# DetBackplane01.net
KiCad netlist of a schematic drawn in EAGLE
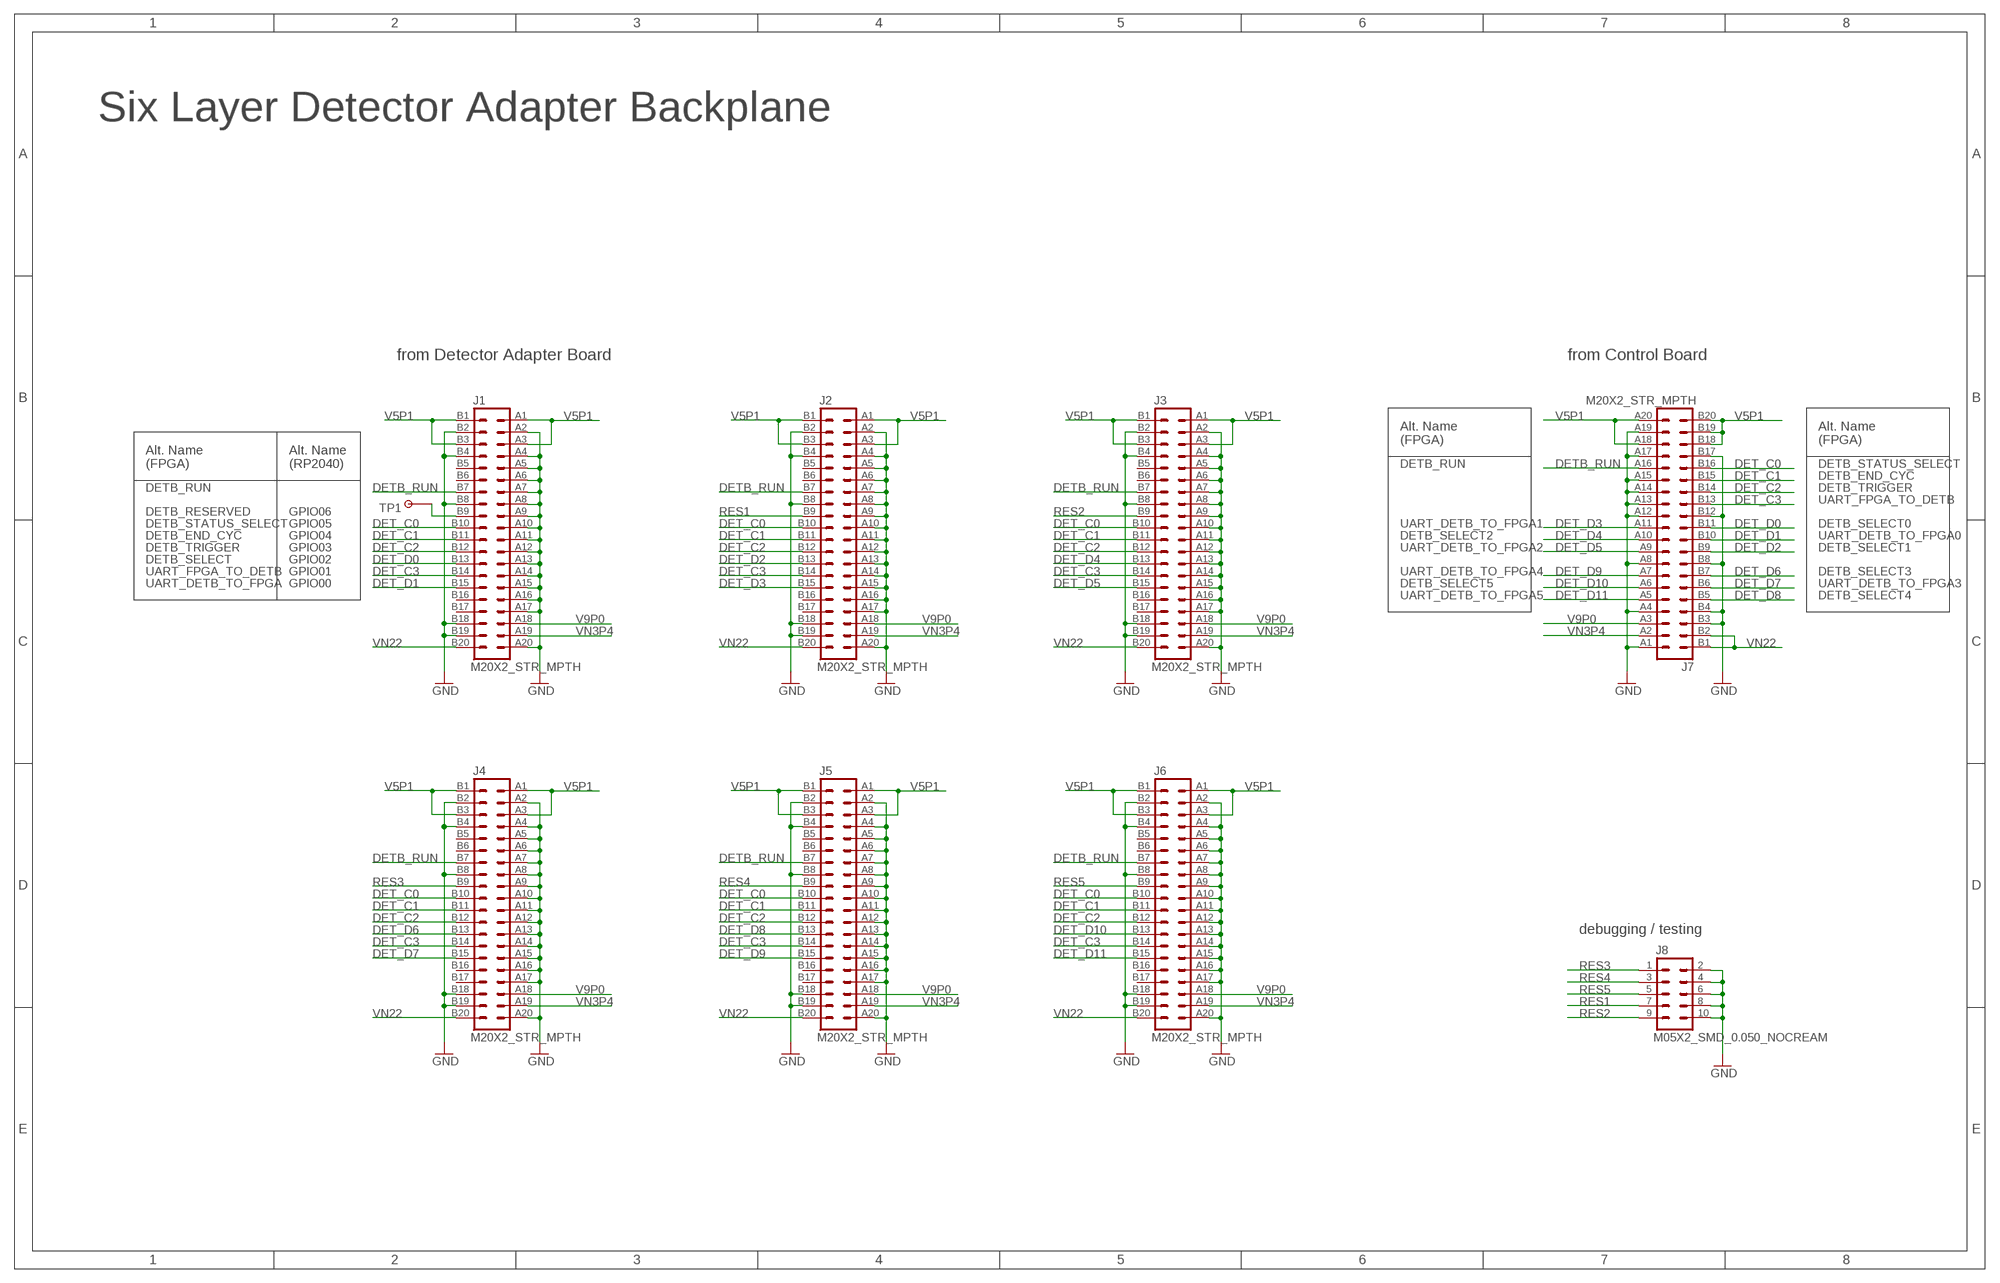
[diagram p0: schematic, sheet 1]

(export (version "E")
  (design (tool "Eeschema 10.0.6"))
  (components
    (comp (ref "J1")
      (value "M20X2_STR_MPTH")
      (footprint "eagle-import:M20X2_HARFLEX_F_STR_MPTH")
      (libsource (lib "eagle-import") (part "M20X2_STR_MPTH"))
    )
    (comp (ref "J2")
      (value "M20X2_STR_MPTH")
      (footprint "eagle-import:M20X2_HARFLEX_F_STR_MPTH")
      (libsource (lib "eagle-import") (part "M20X2_STR_MPTH"))
    )
    (comp (ref "J3")
      (value "M20X2_STR_MPTH")
      (footprint "eagle-import:M20X2_HARFLEX_F_STR_MPTH")
      (libsource (lib "eagle-import") (part "M20X2_STR_MPTH"))
    )
    (comp (ref "J4")
      (value "M20X2_STR_MPTH")
      (footprint "eagle-import:M20X2_HARFLEX_F_STR_MPTH")
      (libsource (lib "eagle-import") (part "M20X2_STR_MPTH"))
    )
    (comp (ref "J5")
      (value "M20X2_STR_MPTH")
      (footprint "eagle-import:M20X2_HARFLEX_F_STR_MPTH")
      (libsource (lib "eagle-import") (part "M20X2_STR_MPTH"))
    )
    (comp (ref "J6")
      (value "M20X2_STR_MPTH")
      (footprint "eagle-import:M20X2_HARFLEX_F_STR_MPTH")
      (libsource (lib "eagle-import") (part "M20X2_STR_MPTH"))
    )
    (comp (ref "J7")
      (value "M20X2_STR_MPTH")
      (footprint "eagle-import:M20X2_HARFLEX_F_STR_MPTH")
      (libsource (lib "eagle-import") (part "M20X2_STR_MPTH"))
    )
    (comp (ref "J8")
      (value "M05X2_SMD_0.050_NOCREAM")
      (footprint "eagle-import:M05X2_0.050_SMD_NO_CREAM")
      (libsource (lib "eagle-import") (part "M05X2_SMD_0.050_NOCREAM"))
    )
    (comp (ref "TP1")
      (value "TESTPOINT_ROUND")
      (footprint "eagle-import:TESTPAD_ROUND")
      (libsource (lib "eagle-import") (part "TESTPOINT_ROUND"))
    )
  )
  (nets
    (net (code "1") (name "/DETB_RUN") (class "Default")
      (node (ref "J1") (pin "B7") (pinfunction "13_B7") (pintype "passive"))
      (node (ref "J2") (pin "B7") (pinfunction "13_B7") (pintype "passive"))
      (node (ref "J3") (pin "B7") (pinfunction "13_B7") (pintype "passive"))
      (node (ref "J4") (pin "B7") (pinfunction "13_B7") (pintype "passive"))
      (node (ref "J5") (pin "B7") (pinfunction "13_B7") (pintype "passive"))
      (node (ref "J6") (pin "B7") (pinfunction "13_B7") (pintype "passive"))
      (node (ref "J7") (pin "A16") (pinfunction "32_A16") (pintype "passive"))
    )
    (net (code "2") (name "/DET_C0") (class "Default")
      (node (ref "J1") (pin "B10") (pinfunction "19_B10") (pintype "passive"))
      (node (ref "J2") (pin "B10") (pinfunction "19_B10") (pintype "passive"))
      (node (ref "J3") (pin "B10") (pinfunction "19_B10") (pintype "passive"))
      (node (ref "J4") (pin "B10") (pinfunction "19_B10") (pintype "passive"))
      (node (ref "J5") (pin "B10") (pinfunction "19_B10") (pintype "passive"))
      (node (ref "J6") (pin "B10") (pinfunction "19_B10") (pintype "passive"))
      (node (ref "J7") (pin "B16") (pinfunction "31_B16") (pintype "passive"))
    )
    (net (code "3") (name "/DET_C1") (class "Default")
      (node (ref "J1") (pin "B11") (pinfunction "21_B11") (pintype "passive"))
      (node (ref "J2") (pin "B11") (pinfunction "21_B11") (pintype "passive"))
      (node (ref "J3") (pin "B11") (pinfunction "21_B11") (pintype "passive"))
      (node (ref "J4") (pin "B11") (pinfunction "21_B11") (pintype "passive"))
      (node (ref "J5") (pin "B11") (pinfunction "21_B11") (pintype "passive"))
      (node (ref "J6") (pin "B11") (pinfunction "21_B11") (pintype "passive"))
      (node (ref "J7") (pin "B15") (pinfunction "29_B15") (pintype "passive"))
    )
    (net (code "4") (name "/DET_C2") (class "Default")
      (node (ref "J1") (pin "B12") (pinfunction "23_B12") (pintype "passive"))
      (node (ref "J2") (pin "B12") (pinfunction "23_B12") (pintype "passive"))
      (node (ref "J3") (pin "B12") (pinfunction "23_B12") (pintype "passive"))
      (node (ref "J4") (pin "B12") (pinfunction "23_B12") (pintype "passive"))
      (node (ref "J5") (pin "B12") (pinfunction "23_B12") (pintype "passive"))
      (node (ref "J6") (pin "B12") (pinfunction "23_B12") (pintype "passive"))
      (node (ref "J7") (pin "B14") (pinfunction "27_B14") (pintype "passive"))
    )
    (net (code "5") (name "/DET_C3") (class "Default")
      (node (ref "J1") (pin "B14") (pinfunction "27_B14") (pintype "passive"))
      (node (ref "J2") (pin "B14") (pinfunction "27_B14") (pintype "passive"))
      (node (ref "J3") (pin "B14") (pinfunction "27_B14") (pintype "passive"))
      (node (ref "J4") (pin "B14") (pinfunction "27_B14") (pintype "passive"))
      (node (ref "J5") (pin "B14") (pinfunction "27_B14") (pintype "passive"))
      (node (ref "J6") (pin "B14") (pinfunction "27_B14") (pintype "passive"))
      (node (ref "J7") (pin "B13") (pinfunction "25_B13") (pintype "passive"))
    )
    (net (code "6") (name "/DET_D0") (class "Default")
      (node (ref "J1") (pin "B13") (pinfunction "25_B13") (pintype "passive"))
      (node (ref "J7") (pin "B11") (pinfunction "21_B11") (pintype "passive"))
    )
    (net (code "7") (name "/DET_D1") (class "Default")
      (node (ref "J1") (pin "B15") (pinfunction "29_B15") (pintype "passive"))
      (node (ref "J7") (pin "B10") (pinfunction "19_B10") (pintype "passive"))
    )
    (net (code "8") (name "/DET_D2") (class "Default")
      (node (ref "J2") (pin "B13") (pinfunction "25_B13") (pintype "passive"))
      (node (ref "J7") (pin "B9") (pinfunction "17_B9") (pintype "passive"))
    )
    (net (code "9") (name "/DET_D3") (class "Default")
      (node (ref "J2") (pin "B15") (pinfunction "29_B15") (pintype "passive"))
      (node (ref "J7") (pin "A11") (pinfunction "22_A11") (pintype "passive"))
    )
    (net (code "10") (name "/DET_D4") (class "Default")
      (node (ref "J3") (pin "B13") (pinfunction "25_B13") (pintype "passive"))
      (node (ref "J7") (pin "A10") (pinfunction "20_A10") (pintype "passive"))
    )
    (net (code "11") (name "/DET_D5") (class "Default")
      (node (ref "J3") (pin "B15") (pinfunction "29_B15") (pintype "passive"))
      (node (ref "J7") (pin "A9") (pinfunction "18_A9") (pintype "passive"))
    )
    (net (code "12") (name "/DET_D6") (class "Default")
      (node (ref "J4") (pin "B13") (pinfunction "25_B13") (pintype "passive"))
      (node (ref "J7") (pin "B7") (pinfunction "13_B7") (pintype "passive"))
    )
    (net (code "13") (name "/DET_D7") (class "Default")
      (node (ref "J4") (pin "B15") (pinfunction "29_B15") (pintype "passive"))
      (node (ref "J7") (pin "B6") (pinfunction "11_B6") (pintype "passive"))
    )
    (net (code "14") (name "/DET_D8") (class "Default")
      (node (ref "J5") (pin "B13") (pinfunction "25_B13") (pintype "passive"))
      (node (ref "J7") (pin "B5") (pinfunction "9_B5") (pintype "passive"))
    )
    (net (code "15") (name "/DET_D9") (class "Default")
      (node (ref "J5") (pin "B15") (pinfunction "29_B15") (pintype "passive"))
      (node (ref "J7") (pin "A7") (pinfunction "14_A7") (pintype "passive"))
    )
    (net (code "16") (name "/DET_D10") (class "Default")
      (node (ref "J6") (pin "B13") (pinfunction "25_B13") (pintype "passive"))
      (node (ref "J7") (pin "A6") (pinfunction "12_A6") (pintype "passive"))
    )
    (net (code "17") (name "/DET_D11") (class "Default")
      (node (ref "J6") (pin "B15") (pinfunction "29_B15") (pintype "passive"))
      (node (ref "J7") (pin "A5") (pinfunction "10_A5") (pintype "passive"))
    )
    (net (code "18") (name "/RES1") (class "Default")
      (node (ref "J2") (pin "B9") (pinfunction "17_B9") (pintype "passive"))
      (node (ref "J8") (pin "7") (pinfunction "7_7") (pintype "passive"))
    )
    (net (code "19") (name "/RES2") (class "Default")
      (node (ref "J3") (pin "B9") (pinfunction "17_B9") (pintype "passive"))
      (node (ref "J8") (pin "9") (pinfunction "9_9") (pintype "passive"))
    )
    (net (code "20") (name "/RES3") (class "Default")
      (node (ref "J4") (pin "B9") (pinfunction "17_B9") (pintype "passive"))
      (node (ref "J8") (pin "1") (pinfunction "1_1") (pintype "passive"))
    )
    (net (code "21") (name "/RES4") (class "Default")
      (node (ref "J5") (pin "B9") (pinfunction "17_B9") (pintype "passive"))
      (node (ref "J8") (pin "3") (pinfunction "3_3") (pintype "passive"))
    )
    (net (code "22") (name "/RES5") (class "Default")
      (node (ref "J6") (pin "B9") (pinfunction "17_B9") (pintype "passive"))
      (node (ref "J8") (pin "5") (pinfunction "5_5") (pintype "passive"))
    )
    (net (code "23") (name "/V5P1") (class "Default")
      (node (ref "J1") (pin "A1") (pinfunction "2_A1") (pintype "passive"))
      (node (ref "J1") (pin "A3") (pinfunction "6_A3") (pintype "passive"))
      (node (ref "J1") (pin "B1") (pinfunction "1_B1") (pintype "passive"))
      (node (ref "J1") (pin "B3") (pinfunction "5_B3") (pintype "passive"))
      (node (ref "J2") (pin "A1") (pinfunction "2_A1") (pintype "passive"))
      (node (ref "J2") (pin "A3") (pinfunction "6_A3") (pintype "passive"))
      (node (ref "J2") (pin "B1") (pinfunction "1_B1") (pintype "passive"))
      (node (ref "J2") (pin "B3") (pinfunction "5_B3") (pintype "passive"))
      (node (ref "J3") (pin "A1") (pinfunction "2_A1") (pintype "passive"))
      (node (ref "J3") (pin "A3") (pinfunction "6_A3") (pintype "passive"))
      (node (ref "J3") (pin "B1") (pinfunction "1_B1") (pintype "passive"))
      (node (ref "J3") (pin "B3") (pinfunction "5_B3") (pintype "passive"))
      (node (ref "J4") (pin "A1") (pinfunction "2_A1") (pintype "passive"))
      (node (ref "J4") (pin "A3") (pinfunction "6_A3") (pintype "passive"))
      (node (ref "J4") (pin "B1") (pinfunction "1_B1") (pintype "passive"))
      (node (ref "J4") (pin "B3") (pinfunction "5_B3") (pintype "passive"))
      (node (ref "J5") (pin "A1") (pinfunction "2_A1") (pintype "passive"))
      (node (ref "J5") (pin "A3") (pinfunction "6_A3") (pintype "passive"))
      (node (ref "J5") (pin "B1") (pinfunction "1_B1") (pintype "passive"))
      (node (ref "J5") (pin "B3") (pinfunction "5_B3") (pintype "passive"))
      (node (ref "J6") (pin "A1") (pinfunction "2_A1") (pintype "passive"))
      (node (ref "J6") (pin "A3") (pinfunction "6_A3") (pintype "passive"))
      (node (ref "J6") (pin "B1") (pinfunction "1_B1") (pintype "passive"))
      (node (ref "J6") (pin "B3") (pinfunction "5_B3") (pintype "passive"))
      (node (ref "J7") (pin "A18") (pinfunction "36_A18") (pintype "passive"))
      (node (ref "J7") (pin "A20") (pinfunction "40_A20") (pintype "passive"))
      (node (ref "J7") (pin "B18") (pinfunction "35_B18") (pintype "passive"))
      (node (ref "J7") (pin "B19") (pinfunction "37_B19") (pintype "passive"))
      (node (ref "J7") (pin "B20") (pinfunction "39_B20") (pintype "passive"))
    )
    (net (code "24") (name "/V9P0") (class "Default")
      (node (ref "J1") (pin "A18") (pinfunction "36_A18") (pintype "passive"))
      (node (ref "J2") (pin "A18") (pinfunction "36_A18") (pintype "passive"))
      (node (ref "J3") (pin "A18") (pinfunction "36_A18") (pintype "passive"))
      (node (ref "J4") (pin "A18") (pinfunction "36_A18") (pintype "passive"))
      (node (ref "J5") (pin "A18") (pinfunction "36_A18") (pintype "passive"))
      (node (ref "J6") (pin "A18") (pinfunction "36_A18") (pintype "passive"))
      (node (ref "J7") (pin "A3") (pinfunction "6_A3") (pintype "passive"))
    )
    (net (code "25") (name "/VN3P4") (class "Default")
      (node (ref "J1") (pin "A19") (pinfunction "38_A19") (pintype "passive"))
      (node (ref "J2") (pin "A19") (pinfunction "38_A19") (pintype "passive"))
      (node (ref "J3") (pin "A19") (pinfunction "38_A19") (pintype "passive"))
      (node (ref "J4") (pin "A19") (pinfunction "38_A19") (pintype "passive"))
      (node (ref "J5") (pin "A19") (pinfunction "38_A19") (pintype "passive"))
      (node (ref "J6") (pin "A19") (pinfunction "38_A19") (pintype "passive"))
      (node (ref "J7") (pin "A2") (pinfunction "4_A2") (pintype "passive"))
    )
    (net (code "26") (name "/VN22") (class "Default")
      (node (ref "J1") (pin "B20") (pinfunction "39_B20") (pintype "passive"))
      (node (ref "J2") (pin "B20") (pinfunction "39_B20") (pintype "passive"))
      (node (ref "J3") (pin "B20") (pinfunction "39_B20") (pintype "passive"))
      (node (ref "J4") (pin "B20") (pinfunction "39_B20") (pintype "passive"))
      (node (ref "J5") (pin "B20") (pinfunction "39_B20") (pintype "passive"))
      (node (ref "J6") (pin "B20") (pinfunction "39_B20") (pintype "passive"))
      (node (ref "J7") (pin "B1") (pinfunction "1_B1") (pintype "passive"))
      (node (ref "J7") (pin "B2") (pinfunction "3_B2") (pintype "passive"))
    )
    (net (code "27") (name "GND") (class "Default")
      (node (ref "J1") (pin "A10") (pinfunction "20_A10") (pintype "passive"))
      (node (ref "J1") (pin "A11") (pinfunction "22_A11") (pintype "passive"))
      (node (ref "J1") (pin "A12") (pinfunction "24_A12") (pintype "passive"))
      (node (ref "J1") (pin "A13") (pinfunction "26_A13") (pintype "passive"))
      (node (ref "J1") (pin "A14") (pinfunction "28_A14") (pintype "passive"))
      (node (ref "J1") (pin "A15") (pinfunction "30_A15") (pintype "passive"))
      (node (ref "J1") (pin "A16") (pinfunction "32_A16") (pintype "passive"))
      (node (ref "J1") (pin "A17") (pinfunction "34_A17") (pintype "passive"))
      (node (ref "J1") (pin "A2") (pinfunction "4_A2") (pintype "passive"))
      (node (ref "J1") (pin "A20") (pinfunction "40_A20") (pintype "passive"))
      (node (ref "J1") (pin "A4") (pinfunction "8_A4") (pintype "passive"))
      (node (ref "J1") (pin "A5") (pinfunction "10_A5") (pintype "passive"))
      (node (ref "J1") (pin "A6") (pinfunction "12_A6") (pintype "passive"))
      (node (ref "J1") (pin "A7") (pinfunction "14_A7") (pintype "passive"))
      (node (ref "J1") (pin "A8") (pinfunction "16_A8") (pintype "passive"))
      (node (ref "J1") (pin "A9") (pinfunction "18_A9") (pintype "passive"))
      (node (ref "J1") (pin "B18") (pinfunction "35_B18") (pintype "passive"))
      (node (ref "J1") (pin "B19") (pinfunction "37_B19") (pintype "passive"))
      (node (ref "J1") (pin "B2") (pinfunction "3_B2") (pintype "passive"))
      (node (ref "J1") (pin "B4") (pinfunction "7_B4") (pintype "passive"))
      (node (ref "J1") (pin "B8") (pinfunction "15_B8") (pintype "passive"))
      (node (ref "J2") (pin "A10") (pinfunction "20_A10") (pintype "passive"))
      (node (ref "J2") (pin "A11") (pinfunction "22_A11") (pintype "passive"))
      (node (ref "J2") (pin "A12") (pinfunction "24_A12") (pintype "passive"))
      (node (ref "J2") (pin "A13") (pinfunction "26_A13") (pintype "passive"))
      (node (ref "J2") (pin "A14") (pinfunction "28_A14") (pintype "passive"))
      (node (ref "J2") (pin "A15") (pinfunction "30_A15") (pintype "passive"))
      (node (ref "J2") (pin "A16") (pinfunction "32_A16") (pintype "passive"))
      (node (ref "J2") (pin "A17") (pinfunction "34_A17") (pintype "passive"))
      (node (ref "J2") (pin "A2") (pinfunction "4_A2") (pintype "passive"))
      (node (ref "J2") (pin "A20") (pinfunction "40_A20") (pintype "passive"))
      (node (ref "J2") (pin "A4") (pinfunction "8_A4") (pintype "passive"))
      (node (ref "J2") (pin "A5") (pinfunction "10_A5") (pintype "passive"))
      (node (ref "J2") (pin "A6") (pinfunction "12_A6") (pintype "passive"))
      (node (ref "J2") (pin "A7") (pinfunction "14_A7") (pintype "passive"))
      (node (ref "J2") (pin "A8") (pinfunction "16_A8") (pintype "passive"))
      (node (ref "J2") (pin "A9") (pinfunction "18_A9") (pintype "passive"))
      (node (ref "J2") (pin "B18") (pinfunction "35_B18") (pintype "passive"))
      (node (ref "J2") (pin "B19") (pinfunction "37_B19") (pintype "passive"))
      (node (ref "J2") (pin "B2") (pinfunction "3_B2") (pintype "passive"))
      (node (ref "J2") (pin "B4") (pinfunction "7_B4") (pintype "passive"))
      (node (ref "J2") (pin "B8") (pinfunction "15_B8") (pintype "passive"))
      (node (ref "J3") (pin "A10") (pinfunction "20_A10") (pintype "passive"))
      (node (ref "J3") (pin "A11") (pinfunction "22_A11") (pintype "passive"))
      (node (ref "J3") (pin "A12") (pinfunction "24_A12") (pintype "passive"))
      (node (ref "J3") (pin "A13") (pinfunction "26_A13") (pintype "passive"))
      (node (ref "J3") (pin "A14") (pinfunction "28_A14") (pintype "passive"))
      (node (ref "J3") (pin "A15") (pinfunction "30_A15") (pintype "passive"))
      (node (ref "J3") (pin "A16") (pinfunction "32_A16") (pintype "passive"))
      (node (ref "J3") (pin "A17") (pinfunction "34_A17") (pintype "passive"))
      (node (ref "J3") (pin "A2") (pinfunction "4_A2") (pintype "passive"))
      (node (ref "J3") (pin "A20") (pinfunction "40_A20") (pintype "passive"))
      (node (ref "J3") (pin "A4") (pinfunction "8_A4") (pintype "passive"))
      (node (ref "J3") (pin "A5") (pinfunction "10_A5") (pintype "passive"))
      (node (ref "J3") (pin "A6") (pinfunction "12_A6") (pintype "passive"))
      (node (ref "J3") (pin "A7") (pinfunction "14_A7") (pintype "passive"))
      (node (ref "J3") (pin "A8") (pinfunction "16_A8") (pintype "passive"))
      (node (ref "J3") (pin "A9") (pinfunction "18_A9") (pintype "passive"))
      (node (ref "J3") (pin "B18") (pinfunction "35_B18") (pintype "passive"))
      (node (ref "J3") (pin "B19") (pinfunction "37_B19") (pintype "passive"))
      (node (ref "J3") (pin "B2") (pinfunction "3_B2") (pintype "passive"))
      (node (ref "J3") (pin "B4") (pinfunction "7_B4") (pintype "passive"))
      (node (ref "J3") (pin "B8") (pinfunction "15_B8") (pintype "passive"))
      (node (ref "J4") (pin "A10") (pinfunction "20_A10") (pintype "passive"))
      (node (ref "J4") (pin "A11") (pinfunction "22_A11") (pintype "passive"))
      (node (ref "J4") (pin "A12") (pinfunction "24_A12") (pintype "passive"))
      (node (ref "J4") (pin "A13") (pinfunction "26_A13") (pintype "passive"))
      (node (ref "J4") (pin "A14") (pinfunction "28_A14") (pintype "passive"))
      (node (ref "J4") (pin "A15") (pinfunction "30_A15") (pintype "passive"))
      (node (ref "J4") (pin "A16") (pinfunction "32_A16") (pintype "passive"))
      (node (ref "J4") (pin "A17") (pinfunction "34_A17") (pintype "passive"))
      (node (ref "J4") (pin "A2") (pinfunction "4_A2") (pintype "passive"))
      (node (ref "J4") (pin "A20") (pinfunction "40_A20") (pintype "passive"))
      (node (ref "J4") (pin "A4") (pinfunction "8_A4") (pintype "passive"))
      (node (ref "J4") (pin "A5") (pinfunction "10_A5") (pintype "passive"))
      (node (ref "J4") (pin "A6") (pinfunction "12_A6") (pintype "passive"))
      (node (ref "J4") (pin "A7") (pinfunction "14_A7") (pintype "passive"))
      (node (ref "J4") (pin "A8") (pinfunction "16_A8") (pintype "passive"))
      (node (ref "J4") (pin "A9") (pinfunction "18_A9") (pintype "passive"))
      (node (ref "J4") (pin "B18") (pinfunction "35_B18") (pintype "passive"))
      (node (ref "J4") (pin "B19") (pinfunction "37_B19") (pintype "passive"))
      (node (ref "J4") (pin "B2") (pinfunction "3_B2") (pintype "passive"))
      (node (ref "J4") (pin "B4") (pinfunction "7_B4") (pintype "passive"))
      (node (ref "J4") (pin "B8") (pinfunction "15_B8") (pintype "passive"))
      (node (ref "J5") (pin "A10") (pinfunction "20_A10") (pintype "passive"))
      (node (ref "J5") (pin "A11") (pinfunction "22_A11") (pintype "passive"))
      (node (ref "J5") (pin "A12") (pinfunction "24_A12") (pintype "passive"))
      (node (ref "J5") (pin "A13") (pinfunction "26_A13") (pintype "passive"))
      (node (ref "J5") (pin "A14") (pinfunction "28_A14") (pintype "passive"))
      (node (ref "J5") (pin "A15") (pinfunction "30_A15") (pintype "passive"))
      (node (ref "J5") (pin "A16") (pinfunction "32_A16") (pintype "passive"))
      (node (ref "J5") (pin "A17") (pinfunction "34_A17") (pintype "passive"))
      (node (ref "J5") (pin "A2") (pinfunction "4_A2") (pintype "passive"))
      (node (ref "J5") (pin "A20") (pinfunction "40_A20") (pintype "passive"))
      (node (ref "J5") (pin "A4") (pinfunction "8_A4") (pintype "passive"))
      (node (ref "J5") (pin "A5") (pinfunction "10_A5") (pintype "passive"))
      (node (ref "J5") (pin "A6") (pinfunction "12_A6") (pintype "passive"))
      (node (ref "J5") (pin "A7") (pinfunction "14_A7") (pintype "passive"))
      (node (ref "J5") (pin "A8") (pinfunction "16_A8") (pintype "passive"))
      (node (ref "J5") (pin "A9") (pinfunction "18_A9") (pintype "passive"))
      (node (ref "J5") (pin "B18") (pinfunction "35_B18") (pintype "passive"))
      (node (ref "J5") (pin "B19") (pinfunction "37_B19") (pintype "passive"))
      (node (ref "J5") (pin "B2") (pinfunction "3_B2") (pintype "passive"))
      (node (ref "J5") (pin "B4") (pinfunction "7_B4") (pintype "passive"))
      (node (ref "J5") (pin "B8") (pinfunction "15_B8") (pintype "passive"))
      (node (ref "J6") (pin "A10") (pinfunction "20_A10") (pintype "passive"))
      (node (ref "J6") (pin "A11") (pinfunction "22_A11") (pintype "passive"))
      (node (ref "J6") (pin "A12") (pinfunction "24_A12") (pintype "passive"))
      (node (ref "J6") (pin "A13") (pinfunction "26_A13") (pintype "passive"))
      (node (ref "J6") (pin "A14") (pinfunction "28_A14") (pintype "passive"))
      (node (ref "J6") (pin "A15") (pinfunction "30_A15") (pintype "passive"))
      (node (ref "J6") (pin "A16") (pinfunction "32_A16") (pintype "passive"))
      (node (ref "J6") (pin "A17") (pinfunction "34_A17") (pintype "passive"))
      (node (ref "J6") (pin "A2") (pinfunction "4_A2") (pintype "passive"))
      (node (ref "J6") (pin "A20") (pinfunction "40_A20") (pintype "passive"))
      (node (ref "J6") (pin "A4") (pinfunction "8_A4") (pintype "passive"))
      (node (ref "J6") (pin "A5") (pinfunction "10_A5") (pintype "passive"))
      (node (ref "J6") (pin "A6") (pinfunction "12_A6") (pintype "passive"))
      (node (ref "J6") (pin "A7") (pinfunction "14_A7") (pintype "passive"))
      (node (ref "J6") (pin "A8") (pinfunction "16_A8") (pintype "passive"))
      (node (ref "J6") (pin "A9") (pinfunction "18_A9") (pintype "passive"))
      (node (ref "J6") (pin "B18") (pinfunction "35_B18") (pintype "passive"))
      (node (ref "J6") (pin "B19") (pinfunction "37_B19") (pintype "passive"))
      (node (ref "J6") (pin "B2") (pinfunction "3_B2") (pintype "passive"))
      (node (ref "J6") (pin "B4") (pinfunction "7_B4") (pintype "passive"))
      (node (ref "J6") (pin "B8") (pinfunction "15_B8") (pintype "passive"))
      (node (ref "J7") (pin "A1") (pinfunction "2_A1") (pintype "passive"))
      (node (ref "J7") (pin "A12") (pinfunction "24_A12") (pintype "passive"))
      (node (ref "J7") (pin "A13") (pinfunction "26_A13") (pintype "passive"))
      (node (ref "J7") (pin "A14") (pinfunction "28_A14") (pintype "passive"))
      (node (ref "J7") (pin "A15") (pinfunction "30_A15") (pintype "passive"))
      (node (ref "J7") (pin "A17") (pinfunction "34_A17") (pintype "passive"))
      (node (ref "J7") (pin "A19") (pinfunction "38_A19") (pintype "passive"))
      (node (ref "J7") (pin "A4") (pinfunction "8_A4") (pintype "passive"))
      (node (ref "J7") (pin "A8") (pinfunction "16_A8") (pintype "passive"))
      (node (ref "J7") (pin "B12") (pinfunction "23_B12") (pintype "passive"))
      (node (ref "J7") (pin "B17") (pinfunction "33_B17") (pintype "passive"))
      (node (ref "J7") (pin "B3") (pinfunction "5_B3") (pintype "passive"))
      (node (ref "J7") (pin "B4") (pinfunction "7_B4") (pintype "passive"))
      (node (ref "J7") (pin "B8") (pinfunction "15_B8") (pintype "passive"))
      (node (ref "J8") (pin "10") (pinfunction "10_10") (pintype "passive"))
      (node (ref "J8") (pin "2") (pinfunction "2_2") (pintype "passive"))
      (node (ref "J8") (pin "4") (pinfunction "4_4") (pintype "passive"))
      (node (ref "J8") (pin "6") (pinfunction "6_6") (pintype "passive"))
      (node (ref "J8") (pin "8") (pinfunction "8_8") (pintype "passive"))
    )
    (net (code "28") (name "Net-(J1-17)") (class "Default")
      (node (ref "J1") (pin "B9") (pinfunction "17_B9") (pintype "passive"))
      (node (ref "TP1") (pin "P$1") (pinfunction "P$1_P$1") (pintype "bidirectional"))
    )
    (net (code "29") (name "unconnected-(J1-9-PadB5)") (class "Default")
      (node (ref "J1") (pin "B5") (pinfunction "9_B5") (pintype "passive"))
    )
    (net (code "30") (name "unconnected-(J1-11-PadB6)") (class "Default")
      (node (ref "J1") (pin "B6") (pinfunction "11_B6") (pintype "passive"))
    )
    (net (code "31") (name "unconnected-(J1-31-PadB16)") (class "Default")
      (node (ref "J1") (pin "B16") (pinfunction "31_B16") (pintype "passive"))
    )
    (net (code "32") (name "unconnected-(J1-33-PadB17)") (class "Default")
      (node (ref "J1") (pin "B17") (pinfunction "33_B17") (pintype "passive"))
    )
    (net (code "33") (name "unconnected-(J2-9-PadB5)") (class "Default")
      (node (ref "J2") (pin "B5") (pinfunction "9_B5") (pintype "passive"))
    )
    (net (code "34") (name "unconnected-(J2-11-PadB6)") (class "Default")
      (node (ref "J2") (pin "B6") (pinfunction "11_B6") (pintype "passive"))
    )
    (net (code "35") (name "unconnected-(J2-31-PadB16)") (class "Default")
      (node (ref "J2") (pin "B16") (pinfunction "31_B16") (pintype "passive"))
    )
    (net (code "36") (name "unconnected-(J2-33-PadB17)") (class "Default")
      (node (ref "J2") (pin "B17") (pinfunction "33_B17") (pintype "passive"))
    )
    (net (code "37") (name "unconnected-(J3-9-PadB5)") (class "Default")
      (node (ref "J3") (pin "B5") (pinfunction "9_B5") (pintype "passive"))
    )
    (net (code "38") (name "unconnected-(J3-11-PadB6)") (class "Default")
      (node (ref "J3") (pin "B6") (pinfunction "11_B6") (pintype "passive"))
    )
    (net (code "39") (name "unconnected-(J3-31-PadB16)") (class "Default")
      (node (ref "J3") (pin "B16") (pinfunction "31_B16") (pintype "passive"))
    )
    (net (code "40") (name "unconnected-(J3-33-PadB17)") (class "Default")
      (node (ref "J3") (pin "B17") (pinfunction "33_B17") (pintype "passive"))
    )
    (net (code "41") (name "unconnected-(J4-9-PadB5)") (class "Default")
      (node (ref "J4") (pin "B5") (pinfunction "9_B5") (pintype "passive"))
    )
    (net (code "42") (name "unconnected-(J4-11-PadB6)") (class "Default")
      (node (ref "J4") (pin "B6") (pinfunction "11_B6") (pintype "passive"))
    )
    (net (code "43") (name "unconnected-(J4-31-PadB16)") (class "Default")
      (node (ref "J4") (pin "B16") (pinfunction "31_B16") (pintype "passive"))
    )
    (net (code "44") (name "unconnected-(J4-33-PadB17)") (class "Default")
      (node (ref "J4") (pin "B17") (pinfunction "33_B17") (pintype "passive"))
    )
    (net (code "45") (name "unconnected-(J5-9-PadB5)") (class "Default")
      (node (ref "J5") (pin "B5") (pinfunction "9_B5") (pintype "passive"))
    )
    (net (code "46") (name "unconnected-(J5-11-PadB6)") (class "Default")
      (node (ref "J5") (pin "B6") (pinfunction "11_B6") (pintype "passive"))
    )
    (net (code "47") (name "unconnected-(J5-31-PadB16)") (class "Default")
      (node (ref "J5") (pin "B16") (pinfunction "31_B16") (pintype "passive"))
    )
    (net (code "48") (name "unconnected-(J5-33-PadB17)") (class "Default")
      (node (ref "J5") (pin "B17") (pinfunction "33_B17") (pintype "passive"))
    )
    (net (code "49") (name "unconnected-(J6-9-PadB5)") (class "Default")
      (node (ref "J6") (pin "B5") (pinfunction "9_B5") (pintype "passive"))
    )
    (net (code "50") (name "unconnected-(J6-11-PadB6)") (class "Default")
      (node (ref "J6") (pin "B6") (pinfunction "11_B6") (pintype "passive"))
    )
    (net (code "51") (name "unconnected-(J6-31-PadB16)") (class "Default")
      (node (ref "J6") (pin "B16") (pinfunction "31_B16") (pintype "passive"))
    )
    (net (code "52") (name "unconnected-(J6-33-PadB17)") (class "Default")
      (node (ref "J6") (pin "B17") (pinfunction "33_B17") (pintype "passive"))
    )
  )
)
